# Stepper_Motor4.net
KiCad netlist of a schematic drawn in Altium Designer
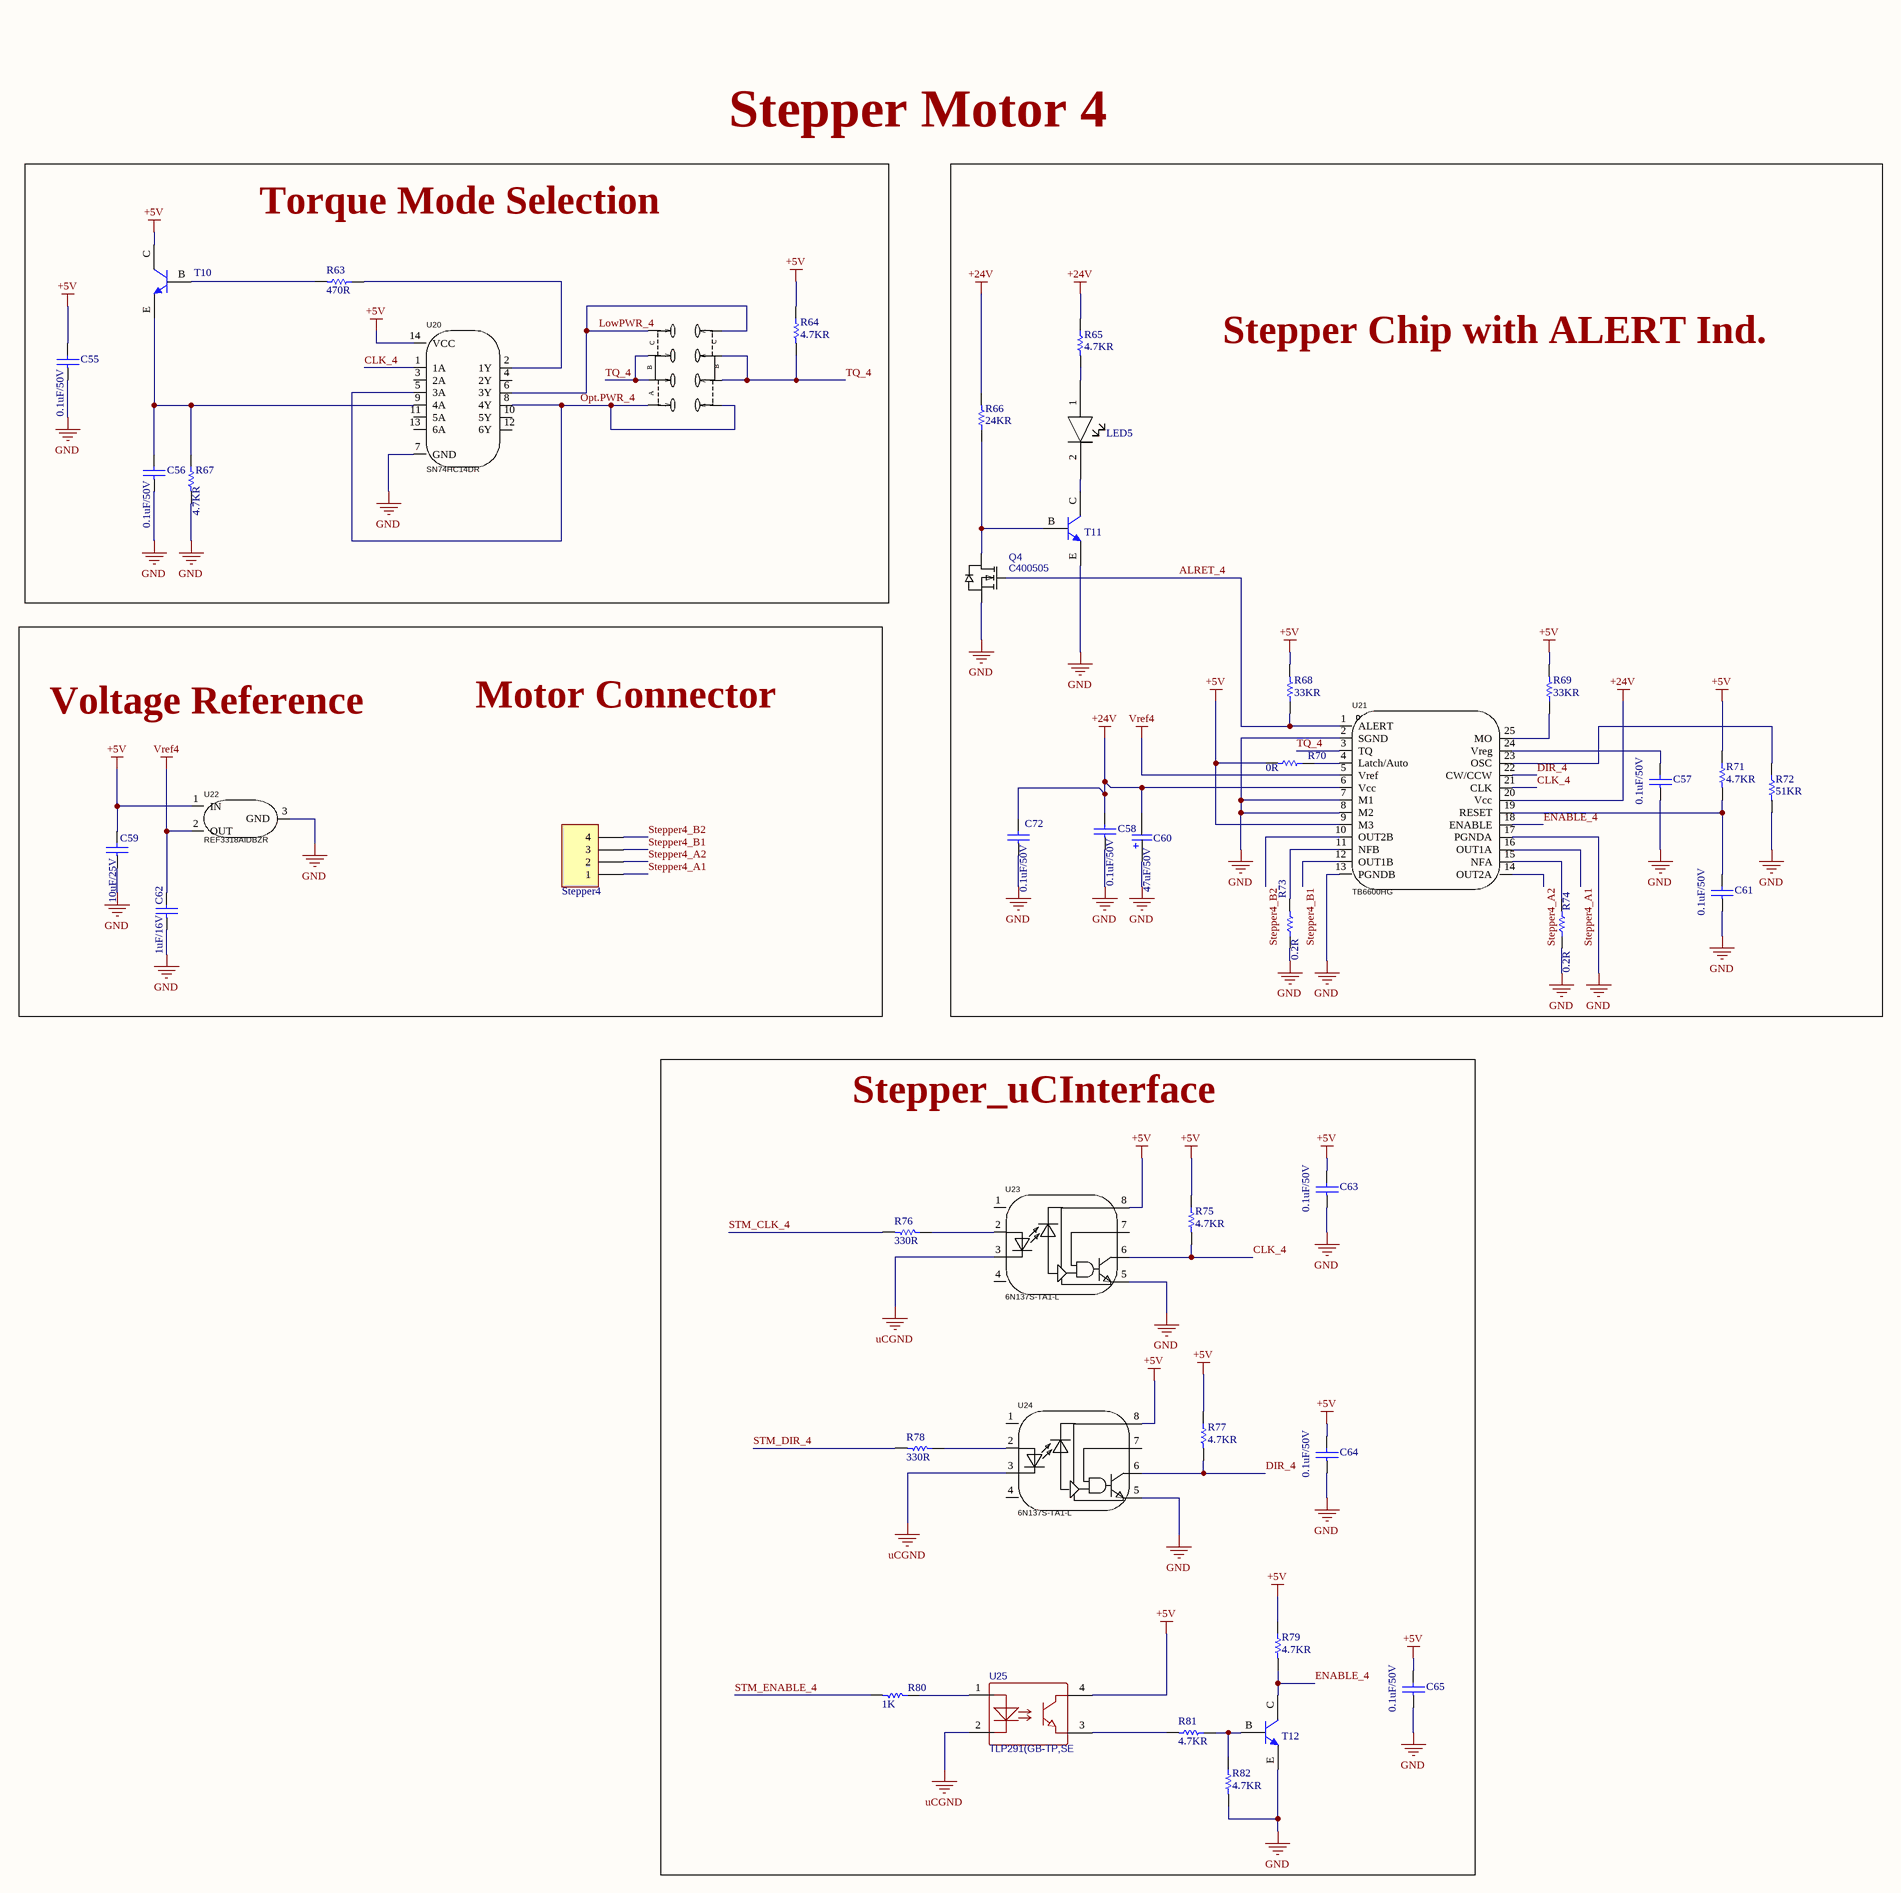
[diagram p0: Stepper Motor4.SchDoc]

(export (version "E")
  (design (tool "Eeschema 10.0.6"))
  (components
    (comp (ref "C55")
      (value "0.1uF/50V")
      (footprint "PCBComponent_1")
      (description "C1591")
      (fields (field (name "CREATED BY") "NourAldin"))
      (libsource (lib "0603 Capacitor") (part "0603 Capacitor"))
    )
    (comp (ref "C56")
      (value "0.1uF/50V")
      (footprint "PCBComponent_1")
      (description "C1591")
      (fields (field (name "CREATED BY") "NourAldin"))
      (libsource (lib "0603 Capacitor") (part "0603 Capacitor"))
    )
    (comp (ref "C57")
      (value "0.1uF/50V")
      (footprint "PCBComponent_1")
      (description "C1591")
      (fields (field (name "CREATED BY") "NourAldin"))
      (libsource (lib "0603 Capacitor") (part "0603 Capacitor"))
    )
    (comp (ref "C58")
      (value "0.1uF/50V")
      (footprint "PCBComponent_1")
      (description "C1591")
      (fields (field (name "CREATED BY") "NourAldin"))
      (libsource (lib "0603 Capacitor") (part "0603 Capacitor"))
    )
    (comp (ref "C59")
      (value "10uF/25V")
      (footprint "PCBComponent_1")
      (description "C96446")
      (fields (field (name "CREATED BY") "NourAldin"))
      (libsource (lib "0603 Capacitor") (part "0603 Capacitor"))
    )
    (comp (ref "C60")
      (value "47uF/50V")
      (footprint "CAPLEAD_D6.3mm")
      (description "C45100")
      (fields
        (field (name "MANUFACTURER") "KEMET")
        (field (name "MANUFACTURER PART NUMBER") "A759EQ475M2AAAE160")
      )
      (libsource (lib "GlobalLib") (part "A759EQ475M2AAAE160"))
    )
    (comp (ref "C61")
      (value "0.1uF/50V")
      (footprint "PCBComponent_1")
      (description "C1591")
      (fields (field (name "CREATED BY") "NourAldin"))
      (libsource (lib "0603 Capacitor") (part "0603 Capacitor"))
    )
    (comp (ref "C62")
      (value "1uF/16V")
      (footprint "PCBComponent_1")
      (description "C1592")
      (fields (field (name "CREATED BY") "NourAldin"))
      (libsource (lib "0603 Capacitor") (part "0603 Capacitor"))
    )
    (comp (ref "C63")
      (value "0.1uF/50V")
      (footprint "PCBComponent_1")
      (description "C1591")
      (fields (field (name "CREATED BY") "NourAldin"))
      (libsource (lib "0603 Capacitor") (part "0603 Capacitor"))
    )
    (comp (ref "C64")
      (value "0.1uF/50V")
      (footprint "PCBComponent_1")
      (description "C1591")
      (fields (field (name "CREATED BY") "NourAldin"))
      (libsource (lib "0603 Capacitor") (part "0603 Capacitor"))
    )
    (comp (ref "C65")
      (value "0.1uF/50V")
      (footprint "PCBComponent_1")
      (description "C1591")
      (fields (field (name "CREATED BY") "NourAldin"))
      (libsource (lib "0603 Capacitor") (part "0603 Capacitor"))
    )
    (comp (ref "C72")
      (value "0.1uF/50V")
      (footprint "PCBComponent_1")
      (description "C1591")
      (fields (field (name "CREATED BY") "NourAldin"))
      (libsource (lib "0603 Capacitor") (part "0603 Capacitor"))
    )
    (comp (ref "LED5")
      (value "1206 LED")
      (footprint "1206 LED")
      (description "C434438")
      (fields (field (name "CREATED BY") "NourAldin"))
      (libsource (lib "1206 LED") (part "1206 LED"))
    )
    (comp (ref "Q4")
      (value "C400505")
      (footprint "SOT-23-3_L2.9-W1.3-P1.90-LS2.4-BR")
      (fields
        (field (name "MANUFACTURER") "YANGJIE(扬杰)")
        (field (name "MANUFACTURER PART") "BSS138")
        (field (name "CONTRIBUTOR") "LCSC")
      )
      (libsource (lib "DIVERSE") (part "BSS138_MOSFET"))
    )
    (comp (ref "R63")
      (value "470R")
      (footprint "RESC1608X06N")
      (description "C114669")
      (fields (field (name "CREATED BY") "NourAldin"))
      (libsource (lib "0603 Resistor") (part "0603 Resistor"))
    )
    (comp (ref "R64")
      (value "4.7KR")
      (footprint "R0402")
      (description "C105871")
      (libsource (lib "DIVERSE") (part "0402 Resistor"))
    )
    (comp (ref "R65")
      (value "4.7KR")
      (footprint "R0402")
      (description "C105871")
      (libsource (lib "DIVERSE") (part "0402 Resistor"))
    )
    (comp (ref "R66")
      (value "24KR")
      (footprint "RESC1608X06N")
      (description "C2930081")
      (fields (field (name "CREATED BY") "NourAldin"))
      (libsource (lib "0603 Resistor") (part "0603 Resistor"))
    )
    (comp (ref "R67")
      (value "4.7KR")
      (footprint "R0402")
      (description "C105871")
      (libsource (lib "DIVERSE") (part "0402 Resistor"))
    )
    (comp (ref "R68")
      (value "33KR")
      (footprint "RESC1608X06N")
      (description "C126359")
      (fields (field (name "CREATED BY") "NourAldin"))
      (libsource (lib "0603 Resistor") (part "0603 Resistor"))
    )
    (comp (ref "R69")
      (value "33KR")
      (footprint "RESC1608X06N")
      (description "C126359")
      (fields (field (name "CREATED BY") "NourAldin"))
      (libsource (lib "0603 Resistor") (part "0603 Resistor"))
    )
    (comp (ref "R70")
      (value "0R")
      (footprint "RESC1608X06N")
      (description "C100044")
      (fields (field (name "CREATED BY") "NourAldin"))
      (libsource (lib "0603 Resistor") (part "0603 Resistor"))
    )
    (comp (ref "R71")
      (value "4.7KR")
      (footprint "R0402")
      (description "C105871")
      (libsource (lib "DIVERSE") (part "0402 Resistor"))
    )
    (comp (ref "R72")
      (value "51KR")
      (footprint "R0402")
      (description "C107230")
      (libsource (lib "DIVERSE") (part "0402 Resistor"))
    )
    (comp (ref "R73")
      (value "0.2R")
      (footprint "RESC6431X12N")
      (description "C2903473")
      (fields (field (name "CREATED BY") "NourAldin"))
      (libsource (lib "2512 Resistor") (part "2512 Resistor"))
    )
    (comp (ref "R74")
      (value "0.2R")
      (footprint "RESC6431X12N")
      (description "C2903473")
      (fields (field (name "CREATED BY") "NourAldin"))
      (libsource (lib "2512 Resistor") (part "2512 Resistor"))
    )
    (comp (ref "R75")
      (value "4.7KR")
      (footprint "R0402")
      (description "C105871")
      (libsource (lib "DIVERSE") (part "0402 Resistor"))
    )
    (comp (ref "R76")
      (value "330R")
      (footprint "R0402")
      (description "C105875")
      (libsource (lib "DIVERSE") (part "0402 Resistor"))
    )
    (comp (ref "R77")
      (value "4.7KR")
      (footprint "R0402")
      (description "C105871")
      (libsource (lib "DIVERSE") (part "0402 Resistor"))
    )
    (comp (ref "R78")
      (value "330R")
      (footprint "R0402")
      (description "C105875")
      (libsource (lib "DIVERSE") (part "0402 Resistor"))
    )
    (comp (ref "R79")
      (value "4.7KR")
      (footprint "R0402")
      (description "C105871")
      (libsource (lib "DIVERSE") (part "0402 Resistor"))
    )
    (comp (ref "R80")
      (value "1K")
      (footprint "R0402")
      (description "C106235")
      (libsource (lib "DIVERSE") (part "0402 Resistor"))
    )
    (comp (ref "R81")
      (value "4.7KR")
      (footprint "R0402")
      (description "C105871")
      (libsource (lib "DIVERSE") (part "0402 Resistor"))
    )
    (comp (ref "R82")
      (value "4.7KR")
      (footprint "R0402")
      (description "C105871")
      (libsource (lib "DIVERSE") (part "0402 Resistor"))
    )
    (comp (ref "Stepper4")
      (value "Header 4 Pin Polar")
      (footprint "PCBComponent_1")
      (libsource (lib "Header 4 Pin Polar") (part "Header 4 Pin Polar"))
    )
    (comp (ref "SW4")
      (value "MST23D19G2")
      (footprint "SW-SMD_MST23D19G2")
      (description "C431545")
      (fields (field (name "MANUFACTURER") "SHOU HAN(首韩)"))
      (libsource (lib "LIB") (part "MST23D19G2"))
    )
    (comp (ref "T10")
      (value "MMBT3904 Transistor")
      (footprint "MMBT3904")
      (description "C108429")
      (fields (field (name "CREATED BY") "NourAldin"))
      (libsource (lib "MMBT3904 Transistor") (part "MMBT3904 Transistor"))
    )
    (comp (ref "T11")
      (value "MMBT3904 Transistor")
      (footprint "MMBT3904")
      (description "C108429")
      (fields (field (name "CREATED BY") "NourAldin"))
      (libsource (lib "MMBT3904 Transistor") (part "MMBT3904 Transistor"))
    )
    (comp (ref "T12")
      (value "MMBT3904 Transistor")
      (footprint "MMBT3904")
      (description "C108429")
      (fields (field (name "CREATED BY") "NourAldin"))
      (libsource (lib "MMBT3904 Transistor") (part "MMBT3904 Transistor"))
    )
    (comp (ref "U20")
      (value "SN74HC14DR")
      (footprint "SOIC-14_L8.7-W3.9-P1.27-LS6.0-BL")
      (description "C6820")
      (fields (field (name "MANUFACTURER") "TI(德州仪器)"))
      (libsource (lib "LIB") (part "SN74HC14DR"))
    )
    (comp (ref "U21")
      (value "TB6600HG")
      (footprint "HZIP25-P-1.00F")
      (description "C66042")
      (fields (field (name "MANUFACTURER") "TOSHIBA(东芝)"))
      (libsource (lib "LIB") (part "TB6600HG"))
    )
    (comp (ref "U22")
      (value "REF3318AIDBZR")
      (footprint "SOT-23-3_L2.9-W1.3-P1.90-LS2.4-BR")
      (description "C115877")
      (fields (field (name "MANUFACTURER") "TI(德州仪器)") (field (name "TOLERANCE") "±0.15%"))
      (libsource (lib "LIB") (part "REF3318AIDBZR"))
    )
    (comp (ref "U23")
      (value "6N137S-TA1-L")
      (footprint "SOP-8_L9.8-W6.6-P2.54-LS10.3-BL")
      (description "C92651")
      (fields (field (name "MANUFACTURER") "LITEON(光宝)"))
      (libsource (lib "LIB") (part "6N137S-TA1-L"))
    )
    (comp (ref "U24")
      (value "6N137S-TA1-L")
      (footprint "SOP-8_L9.8-W6.6-P2.54-LS10.3-BL")
      (description "C92651")
      (fields (field (name "MANUFACTURER") "LITEON(光宝)"))
      (libsource (lib "LIB") (part "6N137S-TA1-L"))
    )
    (comp (ref "U25")
      (value "TLP291(GB-TP,SE")
      (footprint "SOP-4-1.27mm")
      (description "C55144")
      (libsource (lib "CO2_Lib") (part "TLP291(GB-TP,SE(T"))
    )
  )
  (nets
    (net (code "1") (name "+5V") (class "Default")
      (node (ref "C55") (pin "2") (pinfunction "2_2") (pintype "passive"))
      (node (ref "C59") (pin "2") (pinfunction "2_2") (pintype "passive"))
      (node (ref "C63") (pin "2") (pinfunction "2_2") (pintype "passive"))
      (node (ref "C64") (pin "2") (pinfunction "2_2") (pintype "passive"))
      (node (ref "C65") (pin "2") (pinfunction "2_2") (pintype "passive"))
      (node (ref "R64") (pin "1") (pinfunction "1_1") (pintype "passive"))
      (node (ref "R68") (pin "2") (pinfunction "2_2") (pintype "passive"))
      (node (ref "R69") (pin "2") (pinfunction "2_2") (pintype "passive"))
      (node (ref "R70") (pin "2") (pinfunction "2_2") (pintype "passive"))
      (node (ref "R71") (pin "1") (pinfunction "1_1") (pintype "passive"))
      (node (ref "R75") (pin "1") (pinfunction "1_1") (pintype "passive"))
      (node (ref "R77") (pin "1") (pinfunction "1_1") (pintype "passive"))
      (node (ref "R79") (pin "1") (pinfunction "1_1") (pintype "passive"))
      (node (ref "T10") (pin "C") (pinfunction "C_C") (pintype "passive"))
      (node (ref "U20") (pin "14") (pinfunction "VCC_14") (pintype "passive"))
      (node (ref "U21") (pin "9") (pinfunction "M3_9") (pintype "passive"))
      (node (ref "U22") (pin "1") (pinfunction "IN_1") (pintype "passive"))
      (node (ref "U23") (pin "8") (pinfunction "8_8") (pintype "passive"))
      (node (ref "U24") (pin "8") (pinfunction "8_8") (pintype "passive"))
      (node (ref "U25") (pin "4") (pinfunction "4_4") (pintype "passive"))
    )
    (net (code "2") (name "+24V") (class "Default")
      (node (ref "C58") (pin "2") (pinfunction "2_2") (pintype "passive"))
      (node (ref "C60") (pin "2") (pinfunction "2_2") (pintype "passive"))
      (node (ref "C72") (pin "2") (pinfunction "2_2") (pintype "passive"))
      (node (ref "R65") (pin "1") (pinfunction "1_1") (pintype "passive"))
      (node (ref "R66") (pin "2") (pinfunction "2_2") (pintype "passive"))
      (node (ref "U21") (pin "20") (pinfunction "Vcc_20") (pintype "passive"))
      (node (ref "U21") (pin "6") (pinfunction "Vcc_6") (pintype "passive"))
    )
    (net (code "3") (name "/ALRET_4") (class "Default")
      (node (ref "Q4") (pin "1") (pinfunction "G_1") (pintype "passive"))
      (node (ref "R68") (pin "1") (pinfunction "1_1") (pintype "passive"))
      (node (ref "U21") (pin "1") (pinfunction "ALERT_1") (pintype "passive"))
    )
    (net (code "4") (name "/CLK_4") (class "Default")
      (node (ref "R75") (pin "2") (pinfunction "2_2") (pintype "passive"))
      (node (ref "U20") (pin "1") (pinfunction "1A_1") (pintype "passive"))
      (node (ref "U21") (pin "21") (pinfunction "CLK_21") (pintype "passive"))
      (node (ref "U23") (pin "6") (pinfunction "6_6") (pintype "passive"))
    )
    (net (code "5") (name "/DIR_4") (class "Default")
      (node (ref "R77") (pin "2") (pinfunction "2_2") (pintype "passive"))
      (node (ref "U21") (pin "22") (pinfunction "CW/CCW_22") (pintype "passive"))
      (node (ref "U24") (pin "6") (pinfunction "6_6") (pintype "passive"))
    )
    (net (code "6") (name "/ENABLE_4") (class "Default")
      (node (ref "R79") (pin "2") (pinfunction "2_2") (pintype "passive"))
      (node (ref "T12") (pin "C") (pinfunction "C_C") (pintype "passive"))
      (node (ref "U21") (pin "18") (pinfunction "ENABLE_18") (pintype "passive"))
    )
    (net (code "7") (name "/LowPWR_4") (class "Default")
      (node (ref "SW4") (pin "4") (pinfunction "4_4") (pintype "passive"))
      (node (ref "SW4") (pin "5") (pinfunction "5_5") (pintype "passive"))
      (node (ref "U20") (pin "6") (pinfunction "3Y_6") (pintype "passive"))
    )
    (net (code "8") (name "/Opt.PWR_4") (class "Default")
      (node (ref "SW4") (pin "1") (pinfunction "1_1") (pintype "passive"))
      (node (ref "SW4") (pin "8") (pinfunction "8_8") (pintype "passive"))
      (node (ref "U20") (pin "5") (pinfunction "3A_5") (pintype "passive"))
      (node (ref "U20") (pin "8") (pinfunction "4Y_8") (pintype "passive"))
    )
    (net (code "9") (name "/STM_CLK_4") (class "Default")
      (node (ref "R76") (pin "2") (pinfunction "2_2") (pintype "passive"))
    )
    (net (code "10") (name "/STM_DIR_4") (class "Default")
      (node (ref "R78") (pin "2") (pinfunction "2_2") (pintype "passive"))
    )
    (net (code "11") (name "/STM_ENABLE_4") (class "Default")
      (node (ref "R80") (pin "2") (pinfunction "2_2") (pintype "passive"))
    )
    (net (code "12") (name "/Stepper4_A1") (class "Default")
      (node (ref "Stepper4") (pin "1") (pinfunction "1_1") (pintype "passive"))
      (node (ref "U21") (pin "16") (pinfunction "OUT1A_16") (pintype "passive"))
    )
    (net (code "13") (name "/Stepper4_A2") (class "Default")
      (node (ref "Stepper4") (pin "2") (pinfunction "2_2") (pintype "passive"))
      (node (ref "U21") (pin "14") (pinfunction "OUT2A_14") (pintype "passive"))
    )
    (net (code "14") (name "/Stepper4_B1") (class "Default")
      (node (ref "Stepper4") (pin "3") (pinfunction "3_3") (pintype "passive"))
      (node (ref "U21") (pin "12") (pinfunction "OUT1B_12") (pintype "passive"))
    )
    (net (code "15") (name "/Stepper4_B2") (class "Default")
      (node (ref "Stepper4") (pin "4") (pinfunction "4_4") (pintype "passive"))
      (node (ref "U21") (pin "10") (pinfunction "OUT2B_10") (pintype "passive"))
    )
    (net (code "16") (name "/TQ_4") (class "Default")
      (node (ref "R64") (pin "2") (pinfunction "2_2") (pintype "passive"))
      (node (ref "SW4") (pin "2") (pinfunction "2_2") (pintype "passive"))
      (node (ref "SW4") (pin "3") (pinfunction "3_3") (pintype "passive"))
      (node (ref "SW4") (pin "6") (pinfunction "6_6") (pintype "passive"))
      (node (ref "SW4") (pin "7") (pinfunction "7_7") (pintype "passive"))
      (node (ref "U21") (pin "3") (pinfunction "TQ_3") (pintype "passive"))
    )
    (net (code "17") (name "GND") (class "Default")
      (node (ref "C55") (pin "1") (pinfunction "1_1") (pintype "passive"))
      (node (ref "C56") (pin "1") (pinfunction "1_1") (pintype "passive"))
      (node (ref "C57") (pin "1") (pinfunction "1_1") (pintype "passive"))
      (node (ref "C58") (pin "1") (pinfunction "1_1") (pintype "passive"))
      (node (ref "C59") (pin "1") (pinfunction "1_1") (pintype "passive"))
      (node (ref "C60") (pin "1") (pinfunction "1_1") (pintype "passive"))
      (node (ref "C61") (pin "1") (pinfunction "1_1") (pintype "passive"))
      (node (ref "C62") (pin "1") (pinfunction "1_1") (pintype "passive"))
      (node (ref "C63") (pin "1") (pinfunction "1_1") (pintype "passive"))
      (node (ref "C64") (pin "1") (pinfunction "1_1") (pintype "passive"))
      (node (ref "C65") (pin "1") (pinfunction "1_1") (pintype "passive"))
      (node (ref "C72") (pin "1") (pinfunction "1_1") (pintype "passive"))
      (node (ref "Q4") (pin "2") (pinfunction "S_2") (pintype "passive"))
      (node (ref "R67") (pin "2") (pinfunction "2_2") (pintype "passive"))
      (node (ref "R72") (pin "2") (pinfunction "2_2") (pintype "passive"))
      (node (ref "R73") (pin "1") (pinfunction "1_1") (pintype "passive"))
      (node (ref "R74") (pin "1") (pinfunction "1_1") (pintype "passive"))
      (node (ref "R82") (pin "2") (pinfunction "2_2") (pintype "passive"))
      (node (ref "T11") (pin "E") (pinfunction "E_E") (pintype "passive"))
      (node (ref "T12") (pin "E") (pinfunction "E_E") (pintype "passive"))
      (node (ref "U20") (pin "7") (pinfunction "GND_7") (pintype "passive"))
      (node (ref "U21") (pin "13") (pinfunction "PGNDB_13") (pintype "passive"))
      (node (ref "U21") (pin "17") (pinfunction "PGNDA_17") (pintype "passive"))
      (node (ref "U21") (pin "2") (pinfunction "SGND_2") (pintype "passive"))
      (node (ref "U21") (pin "7") (pinfunction "M1_7") (pintype "passive"))
      (node (ref "U21") (pin "8") (pinfunction "M2_8") (pintype "passive"))
      (node (ref "U22") (pin "3") (pinfunction "GND_3") (pintype "passive"))
      (node (ref "U23") (pin "5") (pinfunction "5_5") (pintype "passive"))
      (node (ref "U24") (pin "5") (pinfunction "5_5") (pintype "passive"))
    )
    (net (code "18") (name "Net-(LED5-Pad1)") (class "Default")
      (node (ref "LED5") (pin "1") (pinfunction "1_1") (pintype "passive"))
      (node (ref "R65") (pin "2") (pinfunction "2_2") (pintype "passive"))
    )
    (net (code "19") (name "Net-(LED5-Pad2)") (class "Default")
      (node (ref "LED5") (pin "2") (pinfunction "2_2") (pintype "passive"))
      (node (ref "T11") (pin "C") (pinfunction "C_C") (pintype "passive"))
    )
    (net (code "20") (name "Net-(Q4-D)") (class "Default")
      (node (ref "Q4") (pin "3") (pinfunction "D_3") (pintype "passive"))
      (node (ref "R66") (pin "1") (pinfunction "1_1") (pintype "passive"))
      (node (ref "T11") (pin "B") (pinfunction "B_B") (pintype "passive"))
    )
    (net (code "21") (name "Net-(R63-Pad2)") (class "Default")
      (node (ref "R63") (pin "2") (pinfunction "2_2") (pintype "passive"))
      (node (ref "T10") (pin "B") (pinfunction "B_B") (pintype "passive"))
    )
    (net (code "22") (name "Net-(R76-Pad1)") (class "Default")
      (node (ref "R76") (pin "1") (pinfunction "1_1") (pintype "passive"))
      (node (ref "U23") (pin "2") (pinfunction "2_2") (pintype "passive"))
    )
    (net (code "23") (name "Net-(R78-Pad1)") (class "Default")
      (node (ref "R78") (pin "1") (pinfunction "1_1") (pintype "passive"))
      (node (ref "U24") (pin "2") (pinfunction "2_2") (pintype "passive"))
    )
    (net (code "24") (name "Net-(R80-Pad1)") (class "Default")
      (node (ref "R80") (pin "1") (pinfunction "1_1") (pintype "passive"))
      (node (ref "U25") (pin "1") (pinfunction "1_1") (pintype "passive"))
    )
    (net (code "25") (name "Net-(R81-Pad1)") (class "Default")
      (node (ref "R81") (pin "1") (pinfunction "1_1") (pintype "passive"))
      (node (ref "R82") (pin "1") (pinfunction "1_1") (pintype "passive"))
      (node (ref "T12") (pin "B") (pinfunction "B_B") (pintype "passive"))
    )
    (net (code "26") (name "Net-(R81-Pad2)") (class "Default")
      (node (ref "R81") (pin "2") (pinfunction "2_2") (pintype "passive"))
      (node (ref "U25") (pin "3") (pinfunction "3_3") (pintype "passive"))
    )
    (net (code "27") (name "Net-(U20-1Y)") (class "Default")
      (node (ref "R63") (pin "1") (pinfunction "1_1") (pintype "passive"))
      (node (ref "U20") (pin "2") (pinfunction "1Y_2") (pintype "passive"))
    )
    (net (code "28") (name "Net-(U20-4A)") (class "Default")
      (node (ref "C56") (pin "2") (pinfunction "2_2") (pintype "passive"))
      (node (ref "R67") (pin "1") (pinfunction "1_1") (pintype "passive"))
      (node (ref "T10") (pin "E") (pinfunction "E_E") (pintype "passive"))
      (node (ref "U20") (pin "9") (pinfunction "4A_9") (pintype "passive"))
    )
    (net (code "29") (name "Net-(U21-Latch{slash}Auto)") (class "Default")
      (node (ref "R70") (pin "1") (pinfunction "1_1") (pintype "passive"))
      (node (ref "U21") (pin "4") (pinfunction "Latch/Auto_4") (pintype "passive"))
    )
    (net (code "30") (name "Net-(U21-MO)") (class "Default")
      (node (ref "R69") (pin "1") (pinfunction "1_1") (pintype "passive"))
      (node (ref "U21") (pin "25") (pinfunction "MO_25") (pintype "passive"))
    )
    (net (code "31") (name "Net-(U21-NFA)") (class "Default")
      (node (ref "R74") (pin "2") (pinfunction "2_2") (pintype "passive"))
      (node (ref "U21") (pin "15") (pinfunction "NFA_15") (pintype "passive"))
    )
    (net (code "32") (name "Net-(U21-NFB)") (class "Default")
      (node (ref "R73") (pin "2") (pinfunction "2_2") (pintype "passive"))
      (node (ref "U21") (pin "11") (pinfunction "NFB_11") (pintype "passive"))
    )
    (net (code "33") (name "Net-(U21-OSC)") (class "Default")
      (node (ref "R72") (pin "1") (pinfunction "1_1") (pintype "passive"))
      (node (ref "U21") (pin "23") (pinfunction "OSC_23") (pintype "passive"))
    )
    (net (code "34") (name "Net-(U21-RESET)") (class "Default")
      (node (ref "C61") (pin "2") (pinfunction "2_2") (pintype "passive"))
      (node (ref "R71") (pin "2") (pinfunction "2_2") (pintype "passive"))
      (node (ref "U21") (pin "19") (pinfunction "RESET_19") (pintype "passive"))
    )
    (net (code "35") (name "Net-(U21-Vreg)") (class "Default")
      (node (ref "C57") (pin "2") (pinfunction "2_2") (pintype "passive"))
      (node (ref "U21") (pin "24") (pinfunction "Vreg_24") (pintype "passive"))
    )
    (net (code "36") (name "Vref4") (class "Default")
      (node (ref "C62") (pin "2") (pinfunction "2_2") (pintype "passive"))
      (node (ref "U21") (pin "5") (pinfunction "Vref_5") (pintype "passive"))
      (node (ref "U22") (pin "2") (pinfunction "OUT_2") (pintype "passive"))
    )
    (net (code "37") (name "uCGND") (class "Default")
      (node (ref "U23") (pin "3") (pinfunction "3_3") (pintype "passive"))
      (node (ref "U24") (pin "3") (pinfunction "3_3") (pintype "passive"))
      (node (ref "U25") (pin "2") (pinfunction "2_2") (pintype "passive"))
    )
    (net (code "38") (name "unconnected-(U20-2A-Pad3)") (class "Default")
      (node (ref "U20") (pin "3") (pinfunction "2A_3") (pintype "passive"))
    )
    (net (code "39") (name "unconnected-(U20-2Y-Pad4)") (class "Default")
      (node (ref "U20") (pin "4") (pinfunction "2Y_4") (pintype "passive"))
    )
    (net (code "40") (name "unconnected-(U20-5A-Pad11)") (class "Default")
      (node (ref "U20") (pin "11") (pinfunction "5A_11") (pintype "passive"))
    )
    (net (code "41") (name "unconnected-(U20-5Y-Pad10)") (class "Default")
      (node (ref "U20") (pin "10") (pinfunction "5Y_10") (pintype "passive"))
    )
    (net (code "42") (name "unconnected-(U20-6A-Pad13)") (class "Default")
      (node (ref "U20") (pin "13") (pinfunction "6A_13") (pintype "passive"))
    )
    (net (code "43") (name "unconnected-(U20-6Y-Pad12)") (class "Default")
      (node (ref "U20") (pin "12") (pinfunction "6Y_12") (pintype "passive"))
    )
    (net (code "44") (name "unconnected-(U23-NC-Pad1)") (class "Default")
      (node (ref "U23") (pin "1") (pinfunction "NC_1") (pintype "passive"))
    )
    (net (code "45") (name "unconnected-(U23-NC-Pad4)") (class "Default")
      (node (ref "U23") (pin "4") (pinfunction "NC_4") (pintype "passive"))
    )
    (net (code "46") (name "unconnected-(U23-Pad7)") (class "Default")
      (node (ref "U23") (pin "7") (pinfunction "7_7") (pintype "passive"))
    )
    (net (code "47") (name "unconnected-(U24-NC-Pad1)") (class "Default")
      (node (ref "U24") (pin "1") (pinfunction "NC_1") (pintype "passive"))
    )
    (net (code "48") (name "unconnected-(U24-NC-Pad4)") (class "Default")
      (node (ref "U24") (pin "4") (pinfunction "NC_4") (pintype "passive"))
    )
    (net (code "49") (name "unconnected-(U24-Pad7)") (class "Default")
      (node (ref "U24") (pin "7") (pinfunction "7_7") (pintype "passive"))
    )
  )
)
